# MainBoard.net
KiCad netlist of a schematic drawn in Altium Designer
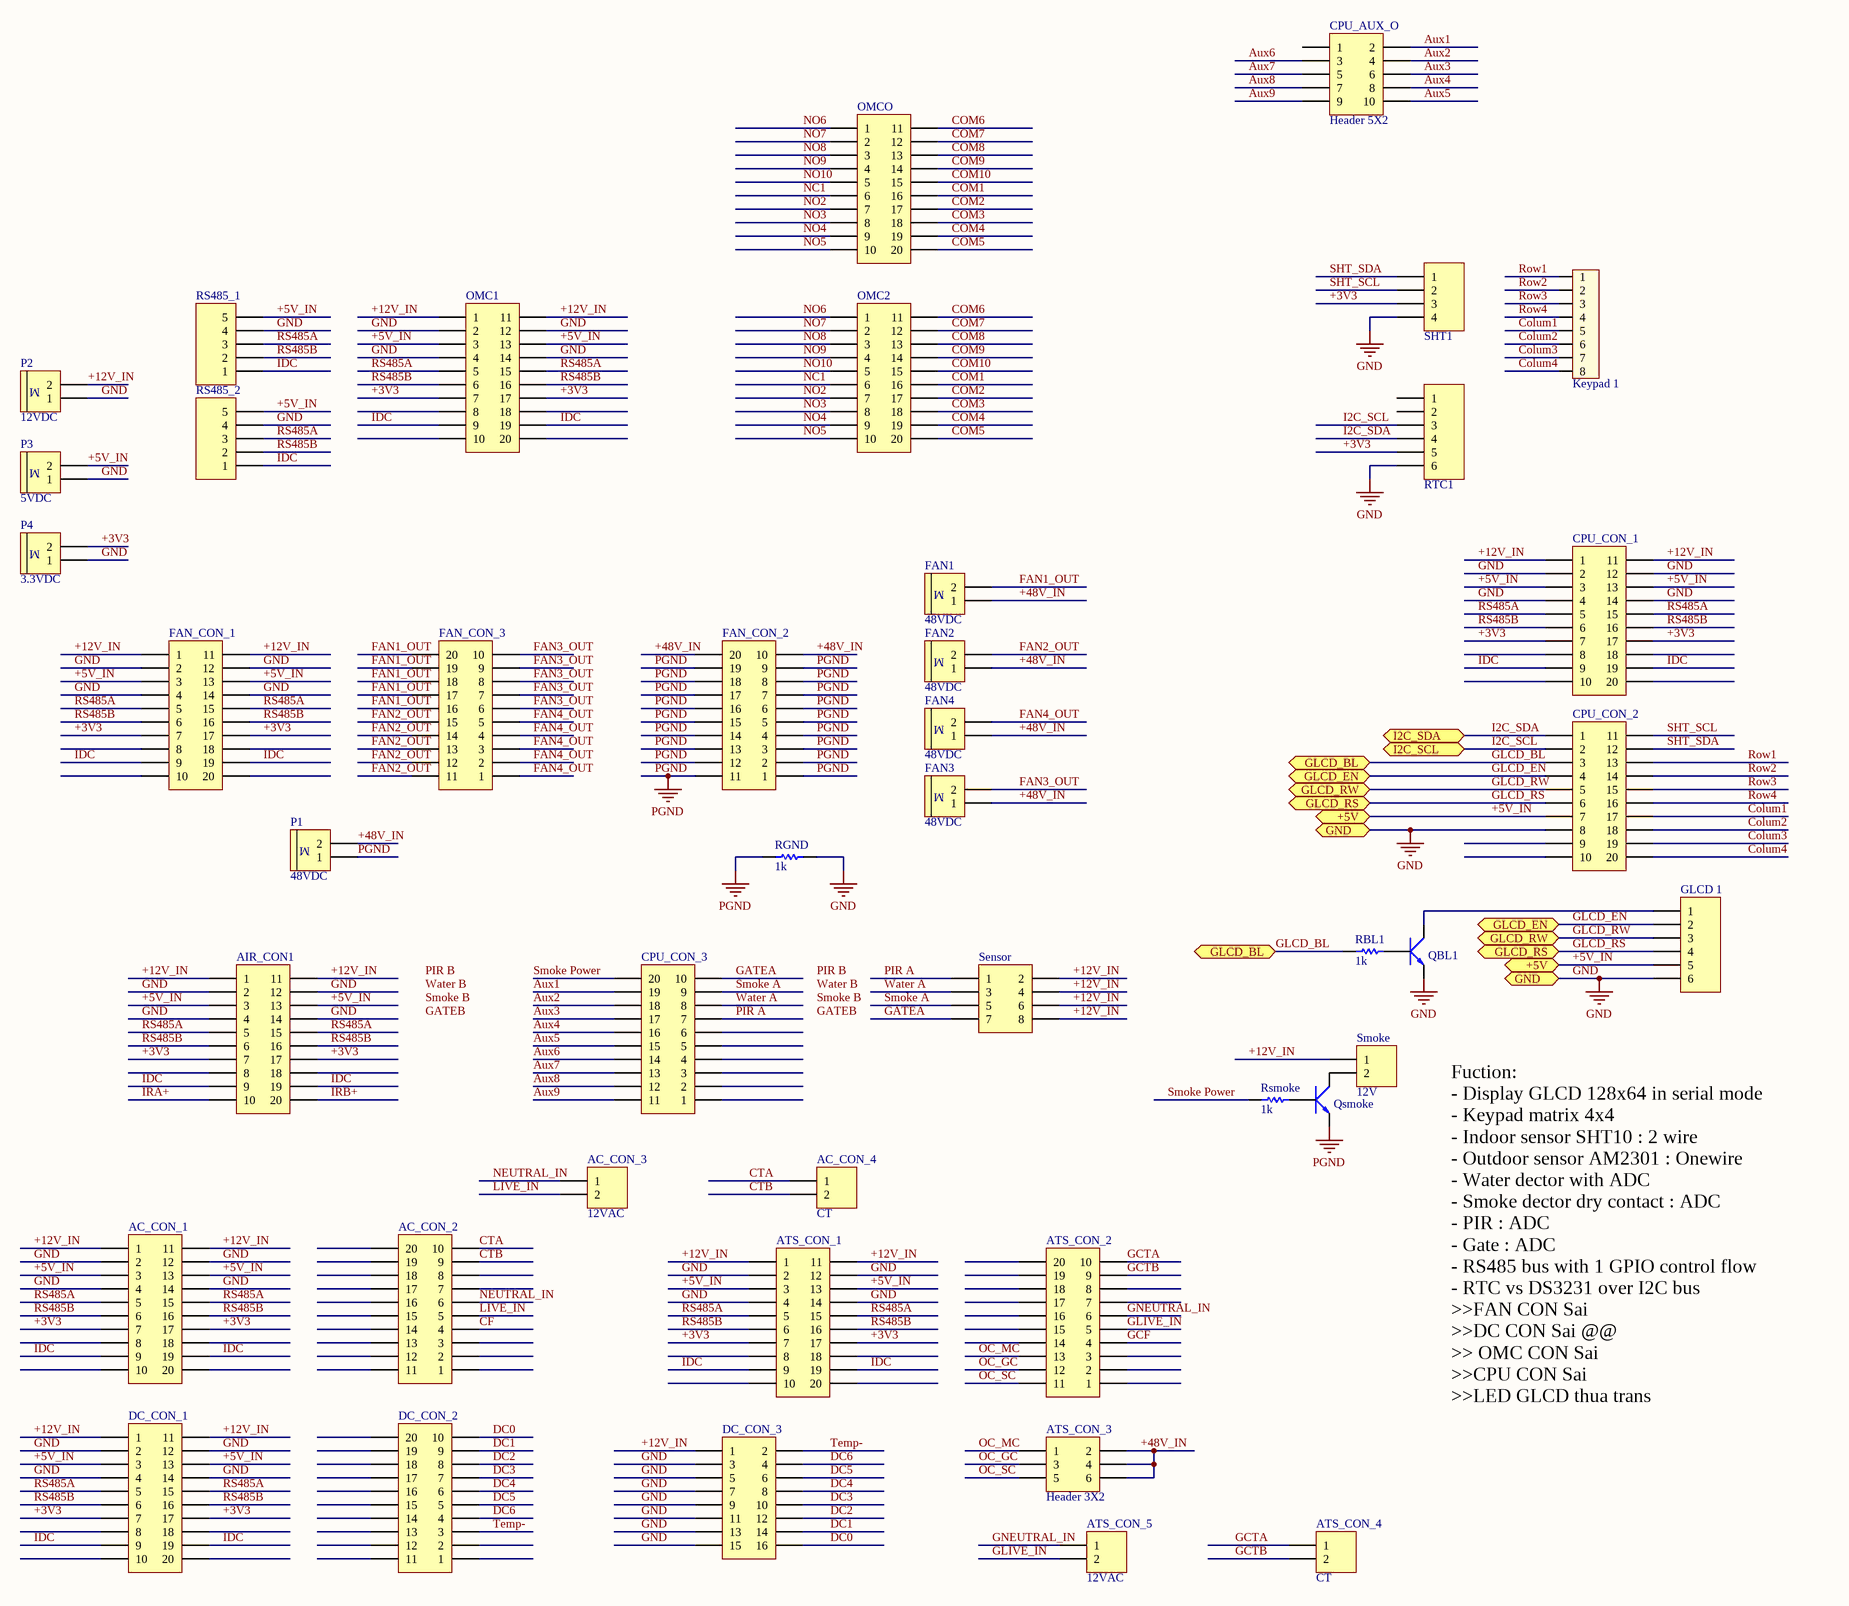
[diagram p0: MainBoard.SchDoc]

(export (version "E")
  (design (tool "Eeschema 10.0.6"))
  (components
    (comp (ref "AC_CON_1")
      (value "Header 10X2A")
      (footprint "HDR2X10_CEN")
      (description "Header, 10-Pin, Dual row")
      (libsource (lib "Miscellaneous Connectors") (part "Header 10X2A"))
    )
    (comp (ref "AC_CON_2")
      (value "Header 10X2A")
      (footprint "HDR2X10_CEN")
      (description "Header, 10-Pin, Dual row")
      (libsource (lib "") (part "Header 10X2A_1"))
    )
    (comp (ref "AC_CON_3")
      (value "12VAC")
      (footprint "HDR1X2")
      (description "Header, 2-Pin")
      (libsource (lib "Miscellaneous Connectors") (part "Header 2"))
    )
    (comp (ref "AC_CON_4")
      (value "CT")
      (footprint "HDR1X2")
      (description "Header, 2-Pin")
      (libsource (lib "Miscellaneous Connectors") (part "Header 2"))
    )
    (comp (ref "AIR_CON1")
      (value "Header 10X2A")
      (footprint "HDR2X10_CEN")
      (description "Header, 10-Pin, Dual row")
      (libsource (lib "Miscellaneous Connectors") (part "Header 10X2A"))
    )
    (comp (ref "ATS_CON_1")
      (value "Header 10X2A")
      (footprint "HDR2X10_CEN")
      (description "Header, 10-Pin, Dual row")
      (libsource (lib "Miscellaneous Connectors") (part "Header 10X2A"))
    )
    (comp (ref "ATS_CON_2")
      (value "Header 10X2A")
      (footprint "HDR2X10_CEN")
      (description "Header, 10-Pin, Dual row")
      (libsource (lib "") (part "Header 10X2A_1"))
    )
    (comp (ref "ATS_CON_3")
      (value "Header 3X2")
      (footprint "HDR2X3")
      (description "Header, 3-Pin, Dual row")
      (libsource (lib "Miscellaneous Connectors") (part "Header 3X2"))
    )
    (comp (ref "ATS_CON_4")
      (value "CT")
      (footprint "HDR1X2")
      (description "Header, 2-Pin")
      (libsource (lib "Miscellaneous Connectors") (part "Header 2"))
    )
    (comp (ref "ATS_CON_5")
      (value "12VAC")
      (footprint "HDR1X2")
      (description "Header, 2-Pin")
      (libsource (lib "Miscellaneous Connectors") (part "Header 2"))
    )
    (comp (ref "CPU_AUX_O")
      (value "Header 5X2")
      (footprint "HDR2X5")
      (description "Header, 5-Pin, Dual row")
      (libsource (lib "Miscellaneous Connectors") (part "Header 5X2"))
    )
    (comp (ref "CPU_CON_1")
      (value "Header 10X2A")
      (footprint "HDR2X10_CEN")
      (description "Header, 10-Pin, Dual row")
      (libsource (lib "Miscellaneous Connectors") (part "Header 10X2A"))
    )
    (comp (ref "CPU_CON_2")
      (value "Header 10X2A")
      (footprint "HDR2X10_CEN")
      (description "Header, 10-Pin, Dual row")
      (libsource (lib "Miscellaneous Connectors") (part "Header 10X2A"))
    )
    (comp (ref "CPU_CON_3")
      (value "Header 10X2A")
      (footprint "HDR2X10_CEN")
      (description "Header, 10-Pin, Dual row")
      (libsource (lib "") (part "Header 10X2A_1"))
    )
    (comp (ref "DC_CON_1")
      (value "Header 10X2A")
      (footprint "HDR2X10_CEN")
      (description "Header, 10-Pin, Dual row")
      (libsource (lib "Miscellaneous Connectors") (part "Header 10X2A"))
    )
    (comp (ref "DC_CON_2")
      (value "Header 10X2A")
      (footprint "HDR2X10_CEN")
      (description "Header, 10-Pin, Dual row")
      (libsource (lib "") (part "Header 10X2A_1"))
    )
    (comp (ref "DC_CON_3")
      (value "Header 8X2")
      (footprint "HDR2X8")
      (description "Header, 8-Pin, Dual row")
      (libsource (lib "Miscellaneous Connectors") (part "Header 8X2"))
    )
    (comp (ref "FAN1")
      (value "48VDC")
      (footprint "Medium - Header 2")
      (description "Header, 2-Pin, Medium")
      (libsource (lib "MH_THU VIEN CHUAN 12-03-2015") (part "Header 2 - M"))
    )
    (comp (ref "FAN2")
      (value "48VDC")
      (footprint "Medium - Header 2")
      (description "Header, 2-Pin, Medium")
      (libsource (lib "MH_THU VIEN CHUAN 12-03-2015") (part "Header 2 - M"))
    )
    (comp (ref "FAN3")
      (value "48VDC")
      (footprint "Medium - Header 2")
      (description "Header, 2-Pin, Medium")
      (libsource (lib "MH_THU VIEN CHUAN 12-03-2015") (part "Header 2 - M"))
    )
    (comp (ref "FAN4")
      (value "48VDC")
      (footprint "Medium - Header 2")
      (description "Header, 2-Pin, Medium")
      (libsource (lib "MH_THU VIEN CHUAN 12-03-2015") (part "Header 2 - M"))
    )
    (comp (ref "FAN_CON_1")
      (value "Header 10X2A")
      (footprint "HDR2X10_CEN")
      (description "Header, 10-Pin, Dual row")
      (libsource (lib "Miscellaneous Connectors") (part "Header 10X2A"))
    )
    (comp (ref "FAN_CON_2")
      (value "Header 10X2A")
      (footprint "HDR2X10_CEN")
      (description "Header, 10-Pin, Dual row")
      (libsource (lib "") (part "Header 10X2A_1"))
    )
    (comp (ref "FAN_CON_3")
      (value "Header 10X2A")
      (footprint "HDR2X10_CEN")
      (description "Header, 10-Pin, Dual row")
      (libsource (lib "") (part "Header 10X2A_1"))
    )
    (comp (ref "GLCD 1")
      (value "Header 6")
      (footprint "HDR1X6")
      (description "Header, 6-Pin")
      (libsource (lib "Miscellaneous Connectors") (part "Header 6"))
    )
    (comp (ref "Keypad 1")
      (value "JP8")
      (footprint "CON8")
      (description "Connector 8")
      (libsource (lib "syhaunguyen") (part "Con8"))
    )
    (comp (ref "OMC1")
      (value "Header 10X2A")
      (footprint "HDR2X10_CEN")
      (description "Header, 10-Pin, Dual row")
      (libsource (lib "Miscellaneous Connectors") (part "Header 10X2A"))
    )
    (comp (ref "OMC2")
      (value "Header 10X2A")
      (footprint "HDR2X10_CEN")
      (description "Header, 10-Pin, Dual row")
      (libsource (lib "Miscellaneous Connectors") (part "Header 10X2A"))
    )
    (comp (ref "OMCO")
      (value "Header 10X2A")
      (footprint "HDR2X10_CEN")
      (description "Header, 10-Pin, Dual row")
      (libsource (lib "Miscellaneous Connectors") (part "Header 10X2A"))
    )
    (comp (ref "P1")
      (value "48VDC")
      (footprint "Medium - Header 2")
      (description "Header, 2-Pin, Medium")
      (libsource (lib "MH_THU VIEN CHUAN 12-03-2015") (part "Header 2 - M"))
    )
    (comp (ref "P2")
      (value "12VDC")
      (footprint "Medium - Header 2")
      (description "Header, 2-Pin, Medium")
      (libsource (lib "MH_THU VIEN CHUAN 12-03-2015") (part "Header 2 - M"))
    )
    (comp (ref "P3")
      (value "5VDC")
      (footprint "Medium - Header 2")
      (description "Header, 2-Pin, Medium")
      (libsource (lib "MH_THU VIEN CHUAN 12-03-2015") (part "Header 2 - M"))
    )
    (comp (ref "P4")
      (value "3.3VDC")
      (footprint "Medium - Header 2")
      (description "Header, 2-Pin, Medium")
      (libsource (lib "MH_THU VIEN CHUAN 12-03-2015") (part "Header 2 - M"))
    )
    (comp (ref "QBL1")
      (value "C828")
      (footprint "QTO-92B")
      (description "Transistor C828 C1815....")
      (libsource (lib "Tuan") (part "NPN"))
    )
    (comp (ref "Qsmoke")
      (value "C828")
      (footprint "QTO-92B")
      (description "Transistor C828 C1815....")
      (libsource (lib "Tuan") (part "NPN"))
    )
    (comp (ref "RBL1")
      (value "1k")
      (footprint "AXIAL-0.4")
      (fields (field (name "Comment") "Res"))
      (libsource (lib "Tuan") (part "Res"))
    )
    (comp (ref "RGND")
      (value "1k")
      (footprint "AXIAL-0.4")
      (fields (field (name "Comment") "Res"))
      (libsource (lib "Tuan") (part "Res"))
    )
    (comp (ref "RS485_1")
      (value "Header 5")
      (footprint "HDR1X5")
      (description "Header, 5-Pin")
      (libsource (lib "Miscellaneous Connectors") (part "Header 5"))
    )
    (comp (ref "RS485_2")
      (value "Header 5")
      (footprint "HDR1X5")
      (description "Header, 5-Pin")
      (libsource (lib "Miscellaneous Connectors") (part "Header 5"))
    )
    (comp (ref "Rsmoke")
      (value "1k")
      (footprint "AXIAL-0.4")
      (fields (field (name "Comment") "Res"))
      (libsource (lib "Tuan") (part "Res"))
    )
    (comp (ref "RTC1")
      (value "Header 6")
      (footprint "heromap:HDR1X6")
      (description "Header, 6-Pin")
      (libsource (lib "heromap") (part "Header 6"))
    )
    (comp (ref "Sensor")
      (value "Header 4X2")
      (footprint "HDR2X4")
      (description "Header, 4-Pin, Dual row")
      (libsource (lib "Miscellaneous Connectors") (part "Header 4X2"))
    )
    (comp (ref "SHT1")
      (value "Header 4")
      (footprint "heromap:HDR1X4")
      (description "Header, 4-Pin")
      (libsource (lib "heromap") (part "Header 4"))
    )
    (comp (ref "Smoke")
      (value "12V")
      (footprint "HDR1X2")
      (description "Header, 2-Pin")
      (libsource (lib "Miscellaneous Connectors") (part "Header 2"))
    )
  )
  (nets
    (net (code "1") (name "/+3V3") (class "Default")
      (node (ref "AC_CON_1") (pin "17") (pinfunction "17_17") (pintype "passive"))
      (node (ref "AC_CON_1") (pin "7") (pinfunction "7_7") (pintype "passive"))
      (node (ref "AIR_CON1") (pin "17") (pinfunction "17_17") (pintype "passive"))
      (node (ref "AIR_CON1") (pin "7") (pinfunction "7_7") (pintype "passive"))
      (node (ref "ATS_CON_1") (pin "17") (pinfunction "17_17") (pintype "passive"))
      (node (ref "ATS_CON_1") (pin "7") (pinfunction "7_7") (pintype "passive"))
      (node (ref "CPU_CON_1") (pin "17") (pinfunction "17_17") (pintype "passive"))
      (node (ref "CPU_CON_1") (pin "7") (pinfunction "7_7") (pintype "passive"))
      (node (ref "DC_CON_1") (pin "17") (pinfunction "17_17") (pintype "passive"))
      (node (ref "DC_CON_1") (pin "7") (pinfunction "7_7") (pintype "passive"))
      (node (ref "FAN_CON_1") (pin "17") (pinfunction "17_17") (pintype "passive"))
      (node (ref "FAN_CON_1") (pin "7") (pinfunction "7_7") (pintype "passive"))
      (node (ref "OMC1") (pin "17") (pinfunction "17_17") (pintype "passive"))
      (node (ref "OMC1") (pin "7") (pinfunction "7_7") (pintype "passive"))
      (node (ref "P4") (pin "2") (pinfunction "2_2") (pintype "passive"))
      (node (ref "RTC1") (pin "5") (pinfunction "5_5") (pintype "passive"))
      (node (ref "SHT1") (pin "3") (pinfunction "3_3") (pintype "passive"))
    )
    (net (code "2") (name "/+5V_IN") (class "Default")
      (node (ref "AC_CON_1") (pin "13") (pinfunction "13_13") (pintype "passive"))
      (node (ref "AC_CON_1") (pin "3") (pinfunction "3_3") (pintype "passive"))
      (node (ref "AIR_CON1") (pin "13") (pinfunction "13_13") (pintype "passive"))
      (node (ref "AIR_CON1") (pin "3") (pinfunction "3_3") (pintype "passive"))
      (node (ref "ATS_CON_1") (pin "13") (pinfunction "13_13") (pintype "passive"))
      (node (ref "ATS_CON_1") (pin "3") (pinfunction "3_3") (pintype "passive"))
      (node (ref "CPU_CON_1") (pin "13") (pinfunction "13_13") (pintype "passive"))
      (node (ref "CPU_CON_1") (pin "3") (pinfunction "3_3") (pintype "passive"))
      (node (ref "CPU_CON_2") (pin "7") (pinfunction "7_7") (pintype "passive"))
      (node (ref "DC_CON_1") (pin "13") (pinfunction "13_13") (pintype "passive"))
      (node (ref "DC_CON_1") (pin "3") (pinfunction "3_3") (pintype "passive"))
      (node (ref "FAN_CON_1") (pin "13") (pinfunction "13_13") (pintype "passive"))
      (node (ref "FAN_CON_1") (pin "3") (pinfunction "3_3") (pintype "passive"))
      (node (ref "GLCD 1") (pin "5") (pinfunction "5_5") (pintype "passive"))
      (node (ref "OMC1") (pin "13") (pinfunction "13_13") (pintype "passive"))
      (node (ref "OMC1") (pin "3") (pinfunction "3_3") (pintype "passive"))
      (node (ref "P3") (pin "2") (pinfunction "2_2") (pintype "passive"))
      (node (ref "RS485_1") (pin "5") (pinfunction "5_5") (pintype "passive"))
      (node (ref "RS485_2") (pin "5") (pinfunction "5_5") (pintype "passive"))
    )
    (net (code "3") (name "/+12V_IN") (class "Default")
      (node (ref "AC_CON_1") (pin "1") (pinfunction "1_1") (pintype "passive"))
      (node (ref "AC_CON_1") (pin "11") (pinfunction "11_11") (pintype "passive"))
      (node (ref "AIR_CON1") (pin "1") (pinfunction "1_1") (pintype "passive"))
      (node (ref "AIR_CON1") (pin "11") (pinfunction "11_11") (pintype "passive"))
      (node (ref "ATS_CON_1") (pin "1") (pinfunction "1_1") (pintype "passive"))
      (node (ref "ATS_CON_1") (pin "11") (pinfunction "11_11") (pintype "passive"))
      (node (ref "CPU_CON_1") (pin "1") (pinfunction "1_1") (pintype "passive"))
      (node (ref "CPU_CON_1") (pin "11") (pinfunction "11_11") (pintype "passive"))
      (node (ref "DC_CON_1") (pin "1") (pinfunction "1_1") (pintype "passive"))
      (node (ref "DC_CON_1") (pin "11") (pinfunction "11_11") (pintype "passive"))
      (node (ref "DC_CON_3") (pin "1") (pinfunction "1_1") (pintype "passive"))
      (node (ref "FAN_CON_1") (pin "1") (pinfunction "1_1") (pintype "passive"))
      (node (ref "FAN_CON_1") (pin "11") (pinfunction "11_11") (pintype "passive"))
      (node (ref "OMC1") (pin "1") (pinfunction "1_1") (pintype "passive"))
      (node (ref "OMC1") (pin "11") (pinfunction "11_11") (pintype "passive"))
      (node (ref "P2") (pin "2") (pinfunction "2_2") (pintype "passive"))
      (node (ref "Sensor") (pin "2") (pinfunction "2_2") (pintype "passive"))
      (node (ref "Sensor") (pin "4") (pinfunction "4_4") (pintype "passive"))
      (node (ref "Sensor") (pin "6") (pinfunction "6_6") (pintype "passive"))
      (node (ref "Sensor") (pin "8") (pinfunction "8_8") (pintype "passive"))
      (node (ref "Smoke") (pin "1") (pinfunction "1_1") (pintype "passive"))
    )
    (net (code "4") (name "/+48V_IN") (class "Default")
      (node (ref "ATS_CON_3") (pin "2") (pinfunction "2_2") (pintype "passive"))
      (node (ref "ATS_CON_3") (pin "4") (pinfunction "4_4") (pintype "passive"))
      (node (ref "ATS_CON_3") (pin "6") (pinfunction "6_6") (pintype "passive"))
      (node (ref "FAN1") (pin "1") (pinfunction "1_1") (pintype "passive"))
      (node (ref "FAN2") (pin "1") (pinfunction "1_1") (pintype "passive"))
      (node (ref "FAN3") (pin "1") (pinfunction "1_1") (pintype "passive"))
      (node (ref "FAN4") (pin "1") (pinfunction "1_1") (pintype "passive"))
      (node (ref "FAN_CON_2") (pin "10") (pinfunction "10_10") (pintype "passive"))
      (node (ref "FAN_CON_2") (pin "20") (pinfunction "20_20") (pintype "passive"))
      (node (ref "P1") (pin "2") (pinfunction "2_2") (pintype "passive"))
    )
    (net (code "5") (name "/Aux1") (class "Default")
      (node (ref "CPU_AUX_O") (pin "2") (pinfunction "2_2") (pintype "passive"))
      (node (ref "CPU_CON_3") (pin "19") (pinfunction "19_19") (pintype "passive"))
    )
    (net (code "6") (name "/Aux2") (class "Default")
      (node (ref "CPU_AUX_O") (pin "4") (pinfunction "4_4") (pintype "passive"))
      (node (ref "CPU_CON_3") (pin "18") (pinfunction "18_18") (pintype "passive"))
    )
    (net (code "7") (name "/Aux3") (class "Default")
      (node (ref "CPU_AUX_O") (pin "6") (pinfunction "6_6") (pintype "passive"))
      (node (ref "CPU_CON_3") (pin "17") (pinfunction "17_17") (pintype "passive"))
    )
    (net (code "8") (name "/Aux4") (class "Default")
      (node (ref "CPU_AUX_O") (pin "8") (pinfunction "8_8") (pintype "passive"))
      (node (ref "CPU_CON_3") (pin "16") (pinfunction "16_16") (pintype "passive"))
    )
    (net (code "9") (name "/Aux5") (class "Default")
      (node (ref "CPU_AUX_O") (pin "10") (pinfunction "10_10") (pintype "passive"))
      (node (ref "CPU_CON_3") (pin "15") (pinfunction "15_15") (pintype "passive"))
    )
    (net (code "10") (name "/Aux6") (class "Default")
      (node (ref "CPU_AUX_O") (pin "3") (pinfunction "3_3") (pintype "passive"))
      (node (ref "CPU_CON_3") (pin "14") (pinfunction "14_14") (pintype "passive"))
    )
    (net (code "11") (name "/Aux7") (class "Default")
      (node (ref "CPU_AUX_O") (pin "5") (pinfunction "5_5") (pintype "passive"))
      (node (ref "CPU_CON_3") (pin "13") (pinfunction "13_13") (pintype "passive"))
    )
    (net (code "12") (name "/Aux8") (class "Default")
      (node (ref "CPU_AUX_O") (pin "7") (pinfunction "7_7") (pintype "passive"))
      (node (ref "CPU_CON_3") (pin "12") (pinfunction "12_12") (pintype "passive"))
    )
    (net (code "13") (name "/Aux9") (class "Default")
      (node (ref "CPU_AUX_O") (pin "9") (pinfunction "9_9") (pintype "passive"))
      (node (ref "CPU_CON_3") (pin "11") (pinfunction "11_11") (pintype "passive"))
    )
    (net (code "14") (name "/CF") (class "Default")
      (node (ref "AC_CON_2") (pin "4") (pinfunction "4_4") (pintype "passive"))
    )
    (net (code "15") (name "/COM1") (class "Default")
      (node (ref "OMC2") (pin "16") (pinfunction "16_16") (pintype "passive"))
      (node (ref "OMCO") (pin "16") (pinfunction "16_16") (pintype "passive"))
    )
    (net (code "16") (name "/COM2") (class "Default")
      (node (ref "OMC2") (pin "17") (pinfunction "17_17") (pintype "passive"))
      (node (ref "OMCO") (pin "17") (pinfunction "17_17") (pintype "passive"))
    )
    (net (code "17") (name "/COM3") (class "Default")
      (node (ref "OMC2") (pin "18") (pinfunction "18_18") (pintype "passive"))
      (node (ref "OMCO") (pin "18") (pinfunction "18_18") (pintype "passive"))
    )
    (net (code "18") (name "/COM4") (class "Default")
      (node (ref "OMC2") (pin "19") (pinfunction "19_19") (pintype "passive"))
      (node (ref "OMCO") (pin "19") (pinfunction "19_19") (pintype "passive"))
    )
    (net (code "19") (name "/COM5") (class "Default")
      (node (ref "OMC2") (pin "20") (pinfunction "20_20") (pintype "passive"))
      (node (ref "OMCO") (pin "20") (pinfunction "20_20") (pintype "passive"))
    )
    (net (code "20") (name "/COM6") (class "Default")
      (node (ref "OMC2") (pin "11") (pinfunction "11_11") (pintype "passive"))
      (node (ref "OMCO") (pin "11") (pinfunction "11_11") (pintype "passive"))
    )
    (net (code "21") (name "/COM7") (class "Default")
      (node (ref "OMC2") (pin "12") (pinfunction "12_12") (pintype "passive"))
      (node (ref "OMCO") (pin "12") (pinfunction "12_12") (pintype "passive"))
    )
    (net (code "22") (name "/COM8") (class "Default")
      (node (ref "OMC2") (pin "13") (pinfunction "13_13") (pintype "passive"))
      (node (ref "OMCO") (pin "13") (pinfunction "13_13") (pintype "passive"))
    )
    (net (code "23") (name "/COM9") (class "Default")
      (node (ref "OMC2") (pin "14") (pinfunction "14_14") (pintype "passive"))
      (node (ref "OMCO") (pin "14") (pinfunction "14_14") (pintype "passive"))
    )
    (net (code "24") (name "/COM10") (class "Default")
      (node (ref "OMC2") (pin "15") (pinfunction "15_15") (pintype "passive"))
      (node (ref "OMCO") (pin "15") (pinfunction "15_15") (pintype "passive"))
    )
    (net (code "25") (name "/CTA") (class "Default")
      (node (ref "AC_CON_2") (pin "10") (pinfunction "10_10") (pintype "passive"))
      (node (ref "AC_CON_4") (pin "1") (pinfunction "1_1") (pintype "passive"))
    )
    (net (code "26") (name "/CTB") (class "Default")
      (node (ref "AC_CON_2") (pin "9") (pinfunction "9_9") (pintype "passive"))
      (node (ref "AC_CON_4") (pin "2") (pinfunction "2_2") (pintype "passive"))
    )
    (net (code "27") (name "/Colum1") (class "Default")
      (node (ref "CPU_CON_2") (pin "17") (pinfunction "17_17") (pintype "passive"))
      (node (ref "Keypad 1") (pin "5") (pinfunction "5_5") (pintype "passive"))
    )
    (net (code "28") (name "/Colum2") (class "Default")
      (node (ref "CPU_CON_2") (pin "18") (pinfunction "18_18") (pintype "passive"))
      (node (ref "Keypad 1") (pin "6") (pinfunction "6_6") (pintype "passive"))
    )
    (net (code "29") (name "/Colum3") (class "Default")
      (node (ref "CPU_CON_2") (pin "19") (pinfunction "19_19") (pintype "passive"))
      (node (ref "Keypad 1") (pin "7") (pinfunction "7_7") (pintype "passive"))
    )
    (net (code "30") (name "/Colum4") (class "Default")
      (node (ref "CPU_CON_2") (pin "20") (pinfunction "20_20") (pintype "passive"))
      (node (ref "Keypad 1") (pin "8") (pinfunction "8_8") (pintype "passive"))
    )
    (net (code "31") (name "/DC0") (class "Default")
      (node (ref "DC_CON_2") (pin "10") (pinfunction "10_10") (pintype "passive"))
      (node (ref "DC_CON_3") (pin "16") (pinfunction "16_16") (pintype "passive"))
    )
    (net (code "32") (name "/DC1") (class "Default")
      (node (ref "DC_CON_2") (pin "9") (pinfunction "9_9") (pintype "passive"))
      (node (ref "DC_CON_3") (pin "14") (pinfunction "14_14") (pintype "passive"))
    )
    (net (code "33") (name "/DC2") (class "Default")
      (node (ref "DC_CON_2") (pin "8") (pinfunction "8_8") (pintype "passive"))
      (node (ref "DC_CON_3") (pin "12") (pinfunction "12_12") (pintype "passive"))
    )
    (net (code "34") (name "/DC3") (class "Default")
      (node (ref "DC_CON_2") (pin "7") (pinfunction "7_7") (pintype "passive"))
      (node (ref "DC_CON_3") (pin "10") (pinfunction "10_10") (pintype "passive"))
    )
    (net (code "35") (name "/DC4") (class "Default")
      (node (ref "DC_CON_2") (pin "6") (pinfunction "6_6") (pintype "passive"))
      (node (ref "DC_CON_3") (pin "8") (pinfunction "8_8") (pintype "passive"))
    )
    (net (code "36") (name "/DC5") (class "Default")
      (node (ref "DC_CON_2") (pin "5") (pinfunction "5_5") (pintype "passive"))
      (node (ref "DC_CON_3") (pin "6") (pinfunction "6_6") (pintype "passive"))
    )
    (net (code "37") (name "/DC6") (class "Default")
      (node (ref "DC_CON_2") (pin "4") (pinfunction "4_4") (pintype "passive"))
      (node (ref "DC_CON_3") (pin "4") (pinfunction "4_4") (pintype "passive"))
    )
    (net (code "38") (name "/FAN1_OUT") (class "Default")
      (node (ref "FAN1") (pin "2") (pinfunction "2_2") (pintype "passive"))
      (node (ref "FAN_CON_3") (pin "16") (pinfunction "16_16") (pintype "passive"))
      (node (ref "FAN_CON_3") (pin "17") (pinfunction "17_17") (pintype "passive"))
      (node (ref "FAN_CON_3") (pin "18") (pinfunction "18_18") (pintype "passive"))
      (node (ref "FAN_CON_3") (pin "19") (pinfunction "19_19") (pintype "passive"))
      (node (ref "FAN_CON_3") (pin "20") (pinfunction "20_20") (pintype "passive"))
    )
    (net (code "39") (name "/FAN2_OUT") (class "Default")
      (node (ref "FAN2") (pin "2") (pinfunction "2_2") (pintype "passive"))
      (node (ref "FAN_CON_3") (pin "11") (pinfunction "11_11") (pintype "passive"))
      (node (ref "FAN_CON_3") (pin "12") (pinfunction "12_12") (pintype "passive"))
      (node (ref "FAN_CON_3") (pin "13") (pinfunction "13_13") (pintype "passive"))
      (node (ref "FAN_CON_3") (pin "14") (pinfunction "14_14") (pintype "passive"))
      (node (ref "FAN_CON_3") (pin "15") (pinfunction "15_15") (pintype "passive"))
    )
    (net (code "40") (name "/FAN3_OUT") (class "Default")
      (node (ref "FAN3") (pin "2") (pinfunction "2_2") (pintype "passive"))
      (node (ref "FAN_CON_3") (pin "10") (pinfunction "10_10") (pintype "passive"))
      (node (ref "FAN_CON_3") (pin "6") (pinfunction "6_6") (pintype "passive"))
      (node (ref "FAN_CON_3") (pin "7") (pinfunction "7_7") (pintype "passive"))
      (node (ref "FAN_CON_3") (pin "8") (pinfunction "8_8") (pintype "passive"))
      (node (ref "FAN_CON_3") (pin "9") (pinfunction "9_9") (pintype "passive"))
    )
    (net (code "41") (name "/FAN4_OUT") (class "Default")
      (node (ref "FAN4") (pin "2") (pinfunction "2_2") (pintype "passive"))
      (node (ref "FAN_CON_3") (pin "1") (pinfunction "1_1") (pintype "passive"))
      (node (ref "FAN_CON_3") (pin "2") (pinfunction "2_2") (pintype "passive"))
      (node (ref "FAN_CON_3") (pin "3") (pinfunction "3_3") (pintype "passive"))
      (node (ref "FAN_CON_3") (pin "4") (pinfunction "4_4") (pintype "passive"))
      (node (ref "FAN_CON_3") (pin "5") (pinfunction "5_5") (pintype "passive"))
    )
    (net (code "42") (name "/GATEA") (class "Default")
      (node (ref "CPU_CON_3") (pin "10") (pinfunction "10_10") (pintype "passive"))
      (node (ref "Sensor") (pin "7") (pinfunction "7_7") (pintype "passive"))
    )
    (net (code "44") (name "/GCF") (class "Default")
      (node (ref "ATS_CON_2") (pin "4") (pinfunction "4_4") (pintype "passive"))
    )
    (net (code "45") (name "/GCTA") (class "Default")
      (node (ref "ATS_CON_2") (pin "10") (pinfunction "10_10") (pintype "passive"))
      (node (ref "ATS_CON_4") (pin "1") (pinfunction "1_1") (pintype "passive"))
    )
    (net (code "46") (name "/GCTB") (class "Default")
      (node (ref "ATS_CON_2") (pin "9") (pinfunction "9_9") (pintype "passive"))
      (node (ref "ATS_CON_4") (pin "2") (pinfunction "2_2") (pintype "passive"))
    )
    (net (code "47") (name "/GLCD_BL") (class "Default")
      (node (ref "CPU_CON_2") (pin "3") (pinfunction "3_3") (pintype "passive"))
      (node (ref "RBL1") (pin "1") (pinfunction "1_1") (pintype "passive"))
    )
    (net (code "48") (name "/GLCD_EN") (class "Default")
      (node (ref "CPU_CON_2") (pin "4") (pinfunction "4_4") (pintype "passive"))
      (node (ref "GLCD 1") (pin "2") (pinfunction "2_2") (pintype "passive"))
    )
    (net (code "49") (name "/GLCD_RS") (class "Default")
      (node (ref "CPU_CON_2") (pin "6") (pinfunction "6_6") (pintype "passive"))
      (node (ref "GLCD 1") (pin "4") (pinfunction "4_4") (pintype "passive"))
    )
    (net (code "50") (name "/GLCD_RW") (class "Default")
      (node (ref "CPU_CON_2") (pin "5") (pinfunction "5_5") (pintype "passive"))
      (node (ref "GLCD 1") (pin "3") (pinfunction "3_3") (pintype "passive"))
    )
    (net (code "51") (name "/GLIVE_IN") (class "Default")
      (node (ref "ATS_CON_2") (pin "5") (pinfunction "5_5") (pintype "passive"))
      (node (ref "ATS_CON_5") (pin "2") (pinfunction "2_2") (pintype "passive"))
    )
    (net (code "52") (name "/GNEUTRAL_IN") (class "Default")
      (node (ref "ATS_CON_2") (pin "6") (pinfunction "6_6") (pintype "passive"))
      (node (ref "ATS_CON_5") (pin "1") (pinfunction "1_1") (pintype "passive"))
    )
    (net (code "53") (name "/I2C_SCL") (class "Default")
      (node (ref "CPU_CON_2") (pin "2") (pinfunction "2_2") (pintype "passive"))
      (node (ref "RTC1") (pin "3") (pinfunction "3_3") (pintype "passive"))
    )
    (net (code "54") (name "/I2C_SDA") (class "Default")
      (node (ref "CPU_CON_2") (pin "1") (pinfunction "1_1") (pintype "passive"))
      (node (ref "RTC1") (pin "4") (pinfunction "4_4") (pintype "passive"))
    )
    (net (code "55") (name "/IDC") (class "Default")
      (node (ref "AC_CON_1") (pin "19") (pinfunction "19_19") (pintype "passive"))
      (node (ref "AC_CON_1") (pin "9") (pinfunction "9_9") (pintype "passive"))
      (node (ref "AIR_CON1") (pin "19") (pinfunction "19_19") (pintype "passive"))
      (node (ref "AIR_CON1") (pin "9") (pinfunction "9_9") (pintype "passive"))
      (node (ref "ATS_CON_1") (pin "19") (pinfunction "19_19") (pintype "passive"))
      (node (ref "ATS_CON_1") (pin "9") (pinfunction "9_9") (pintype "passive"))
      (node (ref "CPU_CON_1") (pin "19") (pinfunction "19_19") (pintype "passive"))
      (node (ref "CPU_CON_1") (pin "9") (pinfunction "9_9") (pintype "passive"))
      (node (ref "DC_CON_1") (pin "19") (pinfunction "19_19") (pintype "passive"))
      (node (ref "DC_CON_1") (pin "9") (pinfunction "9_9") (pintype "passive"))
      (node (ref "FAN_CON_1") (pin "19") (pinfunction "19_19") (pintype "passive"))
      (node (ref "FAN_CON_1") (pin "9") (pinfunction "9_9") (pintype "passive"))
      (node (ref "OMC1") (pin "19") (pinfunction "19_19") (pintype "passive"))
      (node (ref "OMC1") (pin "9") (pinfunction "9_9") (pintype "passive"))
      (node (ref "RS485_1") (pin "1") (pinfunction "1_1") (pintype "passive"))
      (node (ref "RS485_2") (pin "1") (pinfunction "1_1") (pintype "passive"))
    )
    (net (code "56") (name "/IRA+") (class "Default")
      (node (ref "AIR_CON1") (pin "10") (pinfunction "10_10") (pintype "passive"))
    )
    (net (code "57") (name "/IRB+") (class "Default")
      (node (ref "AIR_CON1") (pin "20") (pinfunction "20_20") (pintype "passive"))
    )
    (net (code "58") (name "/LIVE_IN") (class "Default")
      (node (ref "AC_CON_2") (pin "5") (pinfunction "5_5") (pintype "passive"))
      (node (ref "AC_CON_3") (pin "2") (pinfunction "2_2") (pintype "passive"))
    )
    (net (code "59") (name "/NC1") (class "Default")
      (node (ref "OMC2") (pin "6") (pinfunction "6_6") (pintype "passive"))
      (node (ref "OMCO") (pin "6") (pinfunction "6_6") (pintype "passive"))
    )
    (net (code "60") (name "/NEUTRAL_IN") (class "Default")
      (node (ref "AC_CON_2") (pin "6") (pinfunction "6_6") (pintype "passive"))
      (node (ref "AC_CON_3") (pin "1") (pinfunction "1_1") (pintype "passive"))
    )
    (net (code "61") (name "/NO2") (class "Default")
      (node (ref "OMC2") (pin "7") (pinfunction "7_7") (pintype "passive"))
      (node (ref "OMCO") (pin "7") (pinfunction "7_7") (pintype "passive"))
    )
    (net (code "62") (name "/NO3") (class "Default")
      (node (ref "OMC2") (pin "8") (pinfunction "8_8") (pintype "passive"))
      (node (ref "OMCO") (pin "8") (pinfunction "8_8") (pintype "passive"))
    )
    (net (code "63") (name "/NO4") (class "Default")
      (node (ref "OMC2") (pin "9") (pinfunction "9_9") (pintype "passive"))
      (node (ref "OMCO") (pin "9") (pinfunction "9_9") (pintype "passive"))
    )
    (net (code "64") (name "/NO5") (class "Default")
      (node (ref "OMC2") (pin "10") (pinfunction "10_10") (pintype "passive"))
      (node (ref "OMCO") (pin "10") (pinfunction "10_10") (pintype "passive"))
    )
    (net (code "65") (name "/NO6") (class "Default")
      (node (ref "OMC2") (pin "1") (pinfunction "1_1") (pintype "passive"))
      (node (ref "OMCO") (pin "1") (pinfunction "1_1") (pintype "passive"))
    )
    (net (code "66") (name "/NO7") (class "Default")
      (node (ref "OMC2") (pin "2") (pinfunction "2_2") (pintype "passive"))
      (node (ref "OMCO") (pin "2") (pinfunction "2_2") (pintype "passive"))
    )
    (net (code "67") (name "/NO8") (class "Default")
      (node (ref "OMC2") (pin "3") (pinfunction "3_3") (pintype "passive"))
      (node (ref "OMCO") (pin "3") (pinfunction "3_3") (pintype "passive"))
    )
    (net (code "68") (name "/NO9") (class "Default")
      (node (ref "OMC2") (pin "4") (pinfunction "4_4") (pintype "passive"))
      (node (ref "OMCO") (pin "4") (pinfunction "4_4") (pintype "passive"))
    )
    (net (code "69") (name "/NO10") (class "Default")
      (node (ref "OMC2") (pin "5") (pinfunction "5_5") (pintype "passive"))
      (node (ref "OMCO") (pin "5") (pinfunction "5_5") (pintype "passive"))
    )
    (net (code "70") (name "/OC_GC") (class "Default")
      (node (ref "ATS_CON_2") (pin "12") (pinfunction "12_12") (pintype "passive"))
      (node (ref "ATS_CON_3") (pin "3") (pinfunction "3_3") (pintype "passive"))
    )
    (net (code "71") (name "/OC_MC") (class "Default")
      (node (ref "ATS_CON_2") (pin "13") (pinfunction "13_13") (pintype "passive"))
      (node (ref "ATS_CON_3") (pin "1") (pinfunction "1_1") (pintype "passive"))
    )
    (net (code "72") (name "/OC_SC") (class "Default")
      (node (ref "ATS_CON_2") (pin "11") (pinfunction "11_11") (pintype "passive"))
      (node (ref "ATS_CON_3") (pin "5") (pinfunction "5_5") (pintype "passive"))
    )
    (net (code "73") (name "/PIR A") (class "Default")
      (node (ref "CPU_CON_3") (pin "7") (pinfunction "7_7") (pintype "passive"))
      (node (ref "Sensor") (pin "1") (pinfunction "1_1") (pintype "passive"))
    )
    (net (code "75") (name "/RS485A") (class "Default")
      (node (ref "AC_CON_1") (pin "15") (pinfunction "15_15") (pintype "passive"))
      (node (ref "AC_CON_1") (pin "5") (pinfunction "5_5") (pintype "passive"))
      (node (ref "AIR_CON1") (pin "15") (pinfunction "15_15") (pintype "passive"))
      (node (ref "AIR_CON1") (pin "5") (pinfunction "5_5") (pintype "passive"))
      (node (ref "ATS_CON_1") (pin "15") (pinfunction "15_15") (pintype "passive"))
      (node (ref "ATS_CON_1") (pin "5") (pinfunction "5_5") (pintype "passive"))
      (node (ref "CPU_CON_1") (pin "15") (pinfunction "15_15") (pintype "passive"))
      (node (ref "CPU_CON_1") (pin "5") (pinfunction "5_5") (pintype "passive"))
      (node (ref "DC_CON_1") (pin "15") (pinfunction "15_15") (pintype "passive"))
      (node (ref "DC_CON_1") (pin "5") (pinfunction "5_5") (pintype "passive"))
      (node (ref "FAN_CON_1") (pin "15") (pinfunction "15_15") (pintype "passive"))
      (node (ref "FAN_CON_1") (pin "5") (pinfunction "5_5") (pintype "passive"))
      (node (ref "OMC1") (pin "15") (pinfunction "15_15") (pintype "passive"))
      (node (ref "OMC1") (pin "5") (pinfunction "5_5") (pintype "passive"))
      (node (ref "RS485_1") (pin "3") (pinfunction "3_3") (pintype "passive"))
      (node (ref "RS485_2") (pin "3") (pinfunction "3_3") (pintype "passive"))
    )
    (net (code "76") (name "/RS485B") (class "Default")
      (node (ref "AC_CON_1") (pin "16") (pinfunction "16_16") (pintype "passive"))
      (node (ref "AC_CON_1") (pin "6") (pinfunction "6_6") (pintype "passive"))
      (node (ref "AIR_CON1") (pin "16") (pinfunction "16_16") (pintype "passive"))
      (node (ref "AIR_CON1") (pin "6") (pinfunction "6_6") (pintype "passive"))
      (node (ref "ATS_CON_1") (pin "16") (pinfunction "16_16") (pintype "passive"))
      (node (ref "ATS_CON_1") (pin "6") (pinfunction "6_6") (pintype "passive"))
      (node (ref "CPU_CON_1") (pin "16") (pinfunction "16_16") (pintype "passive"))
      (node (ref "CPU_CON_1") (pin "6") (pinfunction "6_6") (pintype "passive"))
      (node (ref "DC_CON_1") (pin "16") (pinfunction "16_16") (pintype "passive"))
      (node (ref "DC_CON_1") (pin "6") (pinfunction "6_6") (pintype "passive"))
      (node (ref "FAN_CON_1") (pin "16") (pinfunction "16_16") (pintype "passive"))
      (node (ref "FAN_CON_1") (pin "6") (pinfunction "6_6") (pintype "passive"))
      (node (ref "OMC1") (pin "16") (pinfunction "16_16") (pintype "passive"))
      (node (ref "OMC1") (pin "6") (pinfunction "6_6") (pintype "passive"))
      (node (ref "RS485_1") (pin "2") (pinfunction "2_2") (pintype "passive"))
      (node (ref "RS485_2") (pin "2") (pinfunction "2_2") (pintype "passive"))
    )
    (net (code "77") (name "/Row1") (class "Default")
      (node (ref "CPU_CON_2") (pin "13") (pinfunction "13_13") (pintype "passive"))
      (node (ref "Keypad 1") (pin "1") (pinfunction "1_1") (pintype "passive"))
    )
    (net (code "78") (name "/Row2") (class "Default")
      (node (ref "CPU_CON_2") (pin "14") (pinfunction "14_14") (pintype "passive"))
      (node (ref "Keypad 1") (pin "2") (pinfunction "2_2") (pintype "passive"))
    )
    (net (code "79") (name "/Row3") (class "Default")
      (node (ref "CPU_CON_2") (pin "15") (pinfunction "15_15") (pintype "passive"))
      (node (ref "Keypad 1") (pin "3") (pinfunction "3_3") (pintype "passive"))
    )
    (net (code "80") (name "/Row4") (class "Default")
      (node (ref "CPU_CON_2") (pin "16") (pinfunction "16_16") (pintype "passive"))
      (node (ref "Keypad 1") (pin "4") (pinfunction "4_4") (pintype "passive"))
    )
    (net (code "81") (name "/SHT_SCL") (class "Default")
      (node (ref "CPU_CON_2") (pin "11") (pinfunction "11_11") (pintype "passive"))
      (node (ref "SHT1") (pin "2") (pinfunction "2_2") (pintype "passive"))
    )
    (net (code "82") (name "/SHT_SDA") (class "Default")
      (node (ref "CPU_CON_2") (pin "12") (pinfunction "12_12") (pintype "passive"))
      (node (ref "SHT1") (pin "1") (pinfunction "1_1") (pintype "passive"))
    )
    (net (code "83") (name "/Smoke A") (class "Default")
      (node (ref "CPU_CON_3") (pin "9") (pinfunction "9_9") (pintype "passive"))
      (node (ref "Sensor") (pin "5") (pinfunction "5_5") (pintype "passive"))
    )
    (net (code "85") (name "/Smoke Power") (class "Default")
      (node (ref "CPU_CON_3") (pin "20") (pinfunction "20_20") (pintype "passive"))
      (node (ref "Rsmoke") (pin "1") (pinfunction "1_1") (pintype "passive"))
    )
    (net (code "86") (name "/Temp-") (class "Default")
      (node (ref "DC_CON_2") (pin "3") (pinfunction "3_3") (pintype "passive"))
      (node (ref "DC_CON_3") (pin "2") (pinfunction "2_2") (pintype "passive"))
    )
    (net (code "87") (name "/Water A") (class "Default")
      (node (ref "CPU_CON_3") (pin "8") (pinfunction "8_8") (pintype "passive"))
      (node (ref "Sensor") (pin "3") (pinfunction "3_3") (pintype "passive"))
    )
    (net (code "89") (name "GND") (class "Default")
      (node (ref "AC_CON_1") (pin "12") (pinfunction "12_12") (pintype "passive"))
      (node (ref "AC_CON_1") (pin "14") (pinfunction "14_14") (pintype "passive"))
      (node (ref "AC_CON_1") (pin "2") (pinfunction "2_2") (pintype "passive"))
      (node (ref "AC_CON_1") (pin "4") (pinfunction "4_4") (pintype "passive"))
      (node (ref "AIR_CON1") (pin "12") (pinfunction "12_12") (pintype "passive"))
      (node (ref "AIR_CON1") (pin "14") (pinfunction "14_14") (pintype "passive"))
      (node (ref "AIR_CON1") (pin "2") (pinfunction "2_2") (pintype "passive"))
      (node (ref "AIR_CON1") (pin "4") (pinfunction "4_4") (pintype "passive"))
      (node (ref "ATS_CON_1") (pin "12") (pinfunction "12_12") (pintype "passive"))
      (node (ref "ATS_CON_1") (pin "14") (pinfunction "14_14") (pintype "passive"))
      (node (ref "ATS_CON_1") (pin "2") (pinfunction "2_2") (pintype "passive"))
      (node (ref "ATS_CON_1") (pin "4") (pinfunction "4_4") (pintype "passive"))
      (node (ref "CPU_CON_1") (pin "12") (pinfunction "12_12") (pintype "passive"))
      (node (ref "CPU_CON_1") (pin "14") (pinfunction "14_14") (pintype "passive"))
      (node (ref "CPU_CON_1") (pin "2") (pinfunction "2_2") (pintype "passive"))
      (node (ref "CPU_CON_1") (pin "4") (pinfunction "4_4") (pintype "passive"))
      (node (ref "CPU_CON_2") (pin "8") (pinfunction "8_8") (pintype "passive"))
      (node (ref "DC_CON_1") (pin "12") (pinfunction "12_12") (pintype "passive"))
      (node (ref "DC_CON_1") (pin "14") (pinfunction "14_14") (pintype "passive"))
      (node (ref "DC_CON_1") (pin "2") (pinfunction "2_2") (pintype "passive"))
      (node (ref "DC_CON_1") (pin "4") (pinfunction "4_4") (pintype "passive"))
      (node (ref "DC_CON_3") (pin "11") (pinfunction "11_11") (pintype "passive"))
      (node (ref "DC_CON_3") (pin "13") (pinfunction "13_13") (pintype "passive"))
      (node (ref "DC_CON_3") (pin "15") (pinfunction "15_15") (pintype "passive"))
      (node (ref "DC_CON_3") (pin "3") (pinfunction "3_3") (pintype "passive"))
      (node (ref "DC_CON_3") (pin "5") (pinfunction "5_5") (pintype "passive"))
      (node (ref "DC_CON_3") (pin "7") (pinfunction "7_7") (pintype "passive"))
      (node (ref "DC_CON_3") (pin "9") (pinfunction "9_9") (pintype "passive"))
      (node (ref "FAN_CON_1") (pin "12") (pinfunction "12_12") (pintype "passive"))
      (node (ref "FAN_CON_1") (pin "14") (pinfunction "14_14") (pintype "passive"))
      (node (ref "FAN_CON_1") (pin "2") (pinfunction "2_2") (pintype "passive"))
      (node (ref "FAN_CON_1") (pin "4") (pinfunction "4_4") (pintype "passive"))
      (node (ref "GLCD 1") (pin "6") (pinfunction "6_6") (pintype "passive"))
      (node (ref "OMC1") (pin "12") (pinfunction "12_12") (pintype "passive"))
      (node (ref "OMC1") (pin "14") (pinfunction "14_14") (pintype "passive"))
      (node (ref "OMC1") (pin "2") (pinfunction "2_2") (pintype "passive"))
      (node (ref "OMC1") (pin "4") (pinfunction "4_4") (pintype "passive"))
      (node (ref "P2") (pin "1") (pinfunction "1_1") (pintype "passive"))
      (node (ref "P3") (pin "1") (pinfunction "1_1") (pintype "passive"))
      (node (ref "P4") (pin "1") (pinfunction "1_1") (pintype "passive"))
      (node (ref "QBL1") (pin "3") (pinfunction "E_3") (pintype "passive"))
      (node (ref "RGND") (pin "2") (pinfunction "2_2") (pintype "passive"))
      (node (ref "RS485_1") (pin "4") (pinfunction "4_4") (pintype "passive"))
      (node (ref "RS485_2") (pin "4") (pinfunction "4_4") (pintype "passive"))
      (node (ref "RTC1") (pin "6") (pinfunction "6_6") (pintype "passive"))
      (node (ref "SHT1") (pin "4") (pinfunction "4_4") (pintype "passive"))
    )
    (net (code "90") (name "Net-(QBL1-B)") (class "Default")
      (node (ref "QBL1") (pin "1") (pinfunction "B_1") (pintype "passive"))
      (node (ref "RBL1") (pin "2") (pinfunction "2_2") (pintype "passive"))
    )
    (net (code "91") (name "Net-(QBL1-C)") (class "Default")
      (node (ref "GLCD 1") (pin "1") (pinfunction "1_1") (pintype "passive"))
      (node (ref "QBL1") (pin "2") (pinfunction "C_2") (pintype "passive"))
    )
    (net (code "92") (name "Net-(Qsmoke-B)") (class "Default")
      (node (ref "Qsmoke") (pin "1") (pinfunction "B_1") (pintype "passive"))
      (node (ref "Rsmoke") (pin "2") (pinfunction "2_2") (pintype "passive"))
    )
    (net (code "93") (name "Net-(Qsmoke-C)") (class "Default")
      (node (ref "Qsmoke") (pin "2") (pinfunction "C_2") (pintype "passive"))
      (node (ref "Smoke") (pin "2") (pinfunction "2_2") (pintype "passive"))
    )
    (net (code "94") (name "PGND") (class "Default")
      (node (ref "FAN_CON_2") (pin "1") (pinfunction "1_1") (pintype "passive"))
      (node (ref "FAN_CON_2") (pin "11") (pinfunction "11_11") (pintype "passive"))
      (node (ref "FAN_CON_2") (pin "12") (pinfunction "12_12") (pintype "passive"))
      (node (ref "FAN_CON_2") (pin "13") (pinfunction "13_13") (pintype "passive"))
      (node (ref "FAN_CON_2") (pin "14") (pinfunction "14_14") (pintype "passive"))
      (node (ref "FAN_CON_2") (pin "15") (pinfunction "15_15") (pintype "passive"))
      (node (ref "FAN_CON_2") (pin "16") (pinfunction "16_16") (pintype "passive"))
      (node (ref "FAN_CON_2") (pin "17") (pinfunction "17_17") (pintype "passive"))
      (node (ref "FAN_CON_2") (pin "18") (pinfunction "18_18") (pintype "passive"))
      (node (ref "FAN_CON_2") (pin "19") (pinfunction "19_19") (pintype "passive"))
      (node (ref "FAN_CON_2") (pin "2") (pinfunction "2_2") (pintype "passive"))
      (node (ref "FAN_CON_2") (pin "3") (pinfunction "3_3") (pintype "passive"))
      (node (ref "FAN_CON_2") (pin "4") (pinfunction "4_4") (pintype "passive"))
      (node (ref "FAN_CON_2") (pin "5") (pinfunction "5_5") (pintype "passive"))
      (node (ref "FAN_CON_2") (pin "6") (pinfunction "6_6") (pintype "passive"))
      (node (ref "FAN_CON_2") (pin "7") (pinfunction "7_7") (pintype "passive"))
      (node (ref "FAN_CON_2") (pin "8") (pinfunction "8_8") (pintype "passive"))
      (node (ref "FAN_CON_2") (pin "9") (pinfunction "9_9") (pintype "passive"))
      (node (ref "P1") (pin "1") (pinfunction "1_1") (pintype "passive"))
      (node (ref "Qsmoke") (pin "3") (pinfunction "E_3") (pintype "passive"))
      (node (ref "RGND") (pin "1") (pinfunction "1_1") (pintype "passive"))
    )
    (net (code "95") (name "unconnected-(AC_CON_1-Pad8)") (class "Default")
      (node (ref "AC_CON_1") (pin "8") (pinfunction "8_8") (pintype "passive"))
    )
    (net (code "96") (name "unconnected-(AC_CON_1-Pad10)") (class "Default")
      (node (ref "AC_CON_1") (pin "10") (pinfunction "10_10") (pintype "passive"))
    )
    (net (code "97") (name "unconnected-(AC_CON_1-Pad18)") (class "Default")
      (node (ref "AC_CON_1") (pin "18") (pinfunction "18_18") (pintype "passive"))
    )
    (net (code "98") (name "unconnected-(AC_CON_1-Pad20)") (class "Default")
      (node (ref "AC_CON_1") (pin "20") (pinfunction "20_20") (pintype "passive"))
    )
    (net (code "99") (name "unconnected-(AC_CON_2-Pad1)") (class "Default")
      (node (ref "AC_CON_2") (pin "1") (pinfunction "1_1") (pintype "passive"))
    )
    (net (code "100") (name "unconnected-(AC_CON_2-Pad2)") (class "Default")
      (node (ref "AC_CON_2") (pin "2") (pinfunction "2_2") (pintype "passive"))
    )
    (net (code "101") (name "unconnected-(AC_CON_2-Pad3)") (class "Default")
      (node (ref "AC_CON_2") (pin "3") (pinfunction "3_3") (pintype "passive"))
    )
    (net (code "102") (name "unconnected-(AC_CON_2-Pad7)") (class "Default")
      (node (ref "AC_CON_2") (pin "7") (pinfunction "7_7") (pintype "passive"))
    )
    (net (code "103") (name "unconnected-(AC_CON_2-Pad8)") (class "Default")
      (node (ref "AC_CON_2") (pin "8") (pinfunction "8_8") (pintype "passive"))
    )
    (net (code "104") (name "unconnected-(AC_CON_2-Pad11)") (class "Default")
      (node (ref "AC_CON_2") (pin "11") (pinfunction "11_11") (pintype "passive"))
    )
    (net (code "105") (name "unconnected-(AC_CON_2-Pad12)") (class "Default")
      (node (ref "AC_CON_2") (pin "12") (pinfunction "12_12") (pintype "passive"))
    )
    (net (code "106") (name "unconnected-(AC_CON_2-Pad13)") (class "Default")
      (node (ref "AC_CON_2") (pin "13") (pinfunction "13_13") (pintype "passive"))
    )
    (net (code "107") (name "unconnected-(AC_CON_2-Pad14)") (class "Default")
      (node (ref "AC_CON_2") (pin "14") (pinfunction "14_14") (pintype "passive"))
    )
    (net (code "108") (name "unconnected-(AC_CON_2-Pad15)") (class "Default")
      (node (ref "AC_CON_2") (pin "15") (pinfunction "15_15") (pintype "passive"))
    )
    (net (code "109") (name "unconnected-(AC_CON_2-Pad16)") (class "Default")
      (node (ref "AC_CON_2") (pin "16") (pinfunction "16_16") (pintype "passive"))
    )
    (net (code "110") (name "unconnected-(AC_CON_2-Pad17)") (class "Default")
      (node (ref "AC_CON_2") (pin "17") (pinfunction "17_17") (pintype "passive"))
    )
    (net (code "111") (name "unconnected-(AC_CON_2-Pad18)") (class "Default")
      (node (ref "AC_CON_2") (pin "18") (pinfunction "18_18") (pintype "passive"))
    )
    (net (code "112") (name "unconnected-(AC_CON_2-Pad19)") (class "Default")
      (node (ref "AC_CON_2") (pin "19") (pinfunction "19_19") (pintype "passive"))
    )
    (net (code "113") (name "unconnected-(AC_CON_2-Pad20)") (class "Default")
      (node (ref "AC_CON_2") (pin "20") (pinfunction "20_20") (pintype "passive"))
    )
    (net (code "114") (name "unconnected-(AIR_CON1-Pad8)") (class "Default")
      (node (ref "AIR_CON1") (pin "8") (pinfunction "8_8") (pintype "passive"))
    )
    (net (code "115") (name "unconnected-(AIR_CON1-Pad18)") (class "Default")
      (node (ref "AIR_CON1") (pin "18") (pinfunction "18_18") (pintype "passive"))
    )
    (net (code "116") (name "unconnected-(ATS_CON_1-Pad8)") (class "Default")
      (node (ref "ATS_CON_1") (pin "8") (pinfunction "8_8") (pintype "passive"))
    )
    (net (code "117") (name "unconnected-(ATS_CON_1-Pad10)") (class "Default")
      (node (ref "ATS_CON_1") (pin "10") (pinfunction "10_10") (pintype "passive"))
    )
    (net (code "118") (name "unconnected-(ATS_CON_1-Pad18)") (class "Default")
      (node (ref "ATS_CON_1") (pin "18") (pinfunction "18_18") (pintype "passive"))
    )
    (net (code "119") (name "unconnected-(ATS_CON_1-Pad20)") (class "Default")
      (node (ref "ATS_CON_1") (pin "20") (pinfunction "20_20") (pintype "passive"))
    )
    (net (code "120") (name "unconnected-(ATS_CON_2-Pad1)") (class "Default")
      (node (ref "ATS_CON_2") (pin "1") (pinfunction "1_1") (pintype "passive"))
    )
    (net (code "121") (name "unconnected-(ATS_CON_2-Pad2)") (class "Default")
      (node (ref "ATS_CON_2") (pin "2") (pinfunction "2_2") (pintype "passive"))
    )
    (net (code "122") (name "unconnected-(ATS_CON_2-Pad3)") (class "Default")
      (node (ref "ATS_CON_2") (pin "3") (pinfunction "3_3") (pintype "passive"))
    )
    (net (code "123") (name "unconnected-(ATS_CON_2-Pad7)") (class "Default")
      (node (ref "ATS_CON_2") (pin "7") (pinfunction "7_7") (pintype "passive"))
    )
    (net (code "124") (name "unconnected-(ATS_CON_2-Pad8)") (class "Default")
      (node (ref "ATS_CON_2") (pin "8") (pinfunction "8_8") (pintype "passive"))
    )
    (net (code "125") (name "unconnected-(ATS_CON_2-Pad14)") (class "Default")
      (node (ref "ATS_CON_2") (pin "14") (pinfunction "14_14") (pintype "passive"))
    )
    (net (code "126") (name "unconnected-(ATS_CON_2-Pad15)") (class "Default")
      (node (ref "ATS_CON_2") (pin "15") (pinfunction "15_15") (pintype "passive"))
    )
    (net (code "127") (name "unconnected-(ATS_CON_2-Pad16)") (class "Default")
      (node (ref "ATS_CON_2") (pin "16") (pinfunction "16_16") (pintype "passive"))
    )
    (net (code "128") (name "unconnected-(ATS_CON_2-Pad17)") (class "Default")
      (node (ref "ATS_CON_2") (pin "17") (pinfunction "17_17") (pintype "passive"))
    )
    (net (code "129") (name "unconnected-(ATS_CON_2-Pad18)") (class "Default")
      (node (ref "ATS_CON_2") (pin "18") (pinfunction "18_18") (pintype "passive"))
    )
    (net (code "130") (name "unconnected-(ATS_CON_2-Pad19)") (class "Default")
      (node (ref "ATS_CON_2") (pin "19") (pinfunction "19_19") (pintype "passive"))
    )
    (net (code "131") (name "unconnected-(ATS_CON_2-Pad20)") (class "Default")
      (node (ref "ATS_CON_2") (pin "20") (pinfunction "20_20") (pintype "passive"))
    )
    (net (code "132") (name "unconnected-(CPU_AUX_O-Pad1)") (class "Default")
      (node (ref "CPU_AUX_O") (pin "1") (pinfunction "1_1") (pintype "passive"))
    )
    (net (code "133") (name "unconnected-(CPU_CON_1-Pad8)") (class "Default")
      (node (ref "CPU_CON_1") (pin "8") (pinfunction "8_8") (pintype "passive"))
    )
    (net (code "134") (name "unconnected-(CPU_CON_1-Pad10)") (class "Default")
      (node (ref "CPU_CON_1") (pin "10") (pinfunction "10_10") (pintype "passive"))
    )
    (net (code "135") (name "unconnected-(CPU_CON_1-Pad18)") (class "Default")
      (node (ref "CPU_CON_1") (pin "18") (pinfunction "18_18") (pintype "passive"))
    )
    (net (code "136") (name "unconnected-(CPU_CON_1-Pad20)") (class "Default")
      (node (ref "CPU_CON_1") (pin "20") (pinfunction "20_20") (pintype "passive"))
    )
    (net (code "137") (name "unconnected-(CPU_CON_2-Pad9)") (class "Default")
      (node (ref "CPU_CON_2") (pin "9") (pinfunction "9_9") (pintype "passive"))
    )
    (net (code "138") (name "unconnected-(CPU_CON_2-Pad10)") (class "Default")
      (node (ref "CPU_CON_2") (pin "10") (pinfunction "10_10") (pintype "passive"))
    )
    (net (code "139") (name "unconnected-(CPU_CON_3-Pad1)") (class "Default")
      (node (ref "CPU_CON_3") (pin "1") (pinfunction "1_1") (pintype "passive"))
    )
    (net (code "140") (name "unconnected-(CPU_CON_3-Pad2)") (class "Default")
      (node (ref "CPU_CON_3") (pin "2") (pinfunction "2_2") (pintype "passive"))
    )
    (net (code "141") (name "unconnected-(CPU_CON_3-Pad3)") (class "Default")
      (node (ref "CPU_CON_3") (pin "3") (pinfunction "3_3") (pintype "passive"))
    )
    (net (code "142") (name "unconnected-(CPU_CON_3-Pad4)") (class "Default")
      (node (ref "CPU_CON_3") (pin "4") (pinfunction "4_4") (pintype "passive"))
    )
    (net (code "143") (name "unconnected-(CPU_CON_3-Pad5)") (class "Default")
      (node (ref "CPU_CON_3") (pin "5") (pinfunction "5_5") (pintype "passive"))
    )
    (net (code "144") (name "unconnected-(CPU_CON_3-Pad6)") (class "Default")
      (node (ref "CPU_CON_3") (pin "6") (pinfunction "6_6") (pintype "passive"))
    )
    (net (code "145") (name "unconnected-(DC_CON_1-Pad8)") (class "Default")
      (node (ref "DC_CON_1") (pin "8") (pinfunction "8_8") (pintype "passive"))
    )
    (net (code "146") (name "unconnected-(DC_CON_1-Pad10)") (class "Default")
      (node (ref "DC_CON_1") (pin "10") (pinfunction "10_10") (pintype "passive"))
    )
    (net (code "147") (name "unconnected-(DC_CON_1-Pad18)") (class "Default")
      (node (ref "DC_CON_1") (pin "18") (pinfunction "18_18") (pintype "passive"))
    )
    (net (code "148") (name "unconnected-(DC_CON_1-Pad20)") (class "Default")
      (node (ref "DC_CON_1") (pin "20") (pinfunction "20_20") (pintype "passive"))
    )
    (net (code "149") (name "unconnected-(DC_CON_2-Pad1)") (class "Default")
      (node (ref "DC_CON_2") (pin "1") (pinfunction "1_1") (pintype "passive"))
    )
    (net (code "150") (name "unconnected-(DC_CON_2-Pad2)") (class "Default")
      (node (ref "DC_CON_2") (pin "2") (pinfunction "2_2") (pintype "passive"))
    )
    (net (code "151") (name "unconnected-(DC_CON_2-Pad11)") (class "Default")
      (node (ref "DC_CON_2") (pin "11") (pinfunction "11_11") (pintype "passive"))
    )
    (net (code "152") (name "unconnected-(DC_CON_2-Pad12)") (class "Default")
      (node (ref "DC_CON_2") (pin "12") (pinfunction "12_12") (pintype "passive"))
    )
    (net (code "153") (name "unconnected-(DC_CON_2-Pad13)") (class "Default")
      (node (ref "DC_CON_2") (pin "13") (pinfunction "13_13") (pintype "passive"))
    )
    (net (code "154") (name "unconnected-(DC_CON_2-Pad14)") (class "Default")
      (node (ref "DC_CON_2") (pin "14") (pinfunction "14_14") (pintype "passive"))
    )
    (net (code "155") (name "unconnected-(DC_CON_2-Pad15)") (class "Default")
      (node (ref "DC_CON_2") (pin "15") (pinfunction "15_15") (pintype "passive"))
    )
    (net (code "156") (name "unconnected-(DC_CON_2-Pad16)") (class "Default")
      (node (ref "DC_CON_2") (pin "16") (pinfunction "16_16") (pintype "passive"))
    )
    (net (code "157") (name "unconnected-(DC_CON_2-Pad17)") (class "Default")
      (node (ref "DC_CON_2") (pin "17") (pinfunction "17_17") (pintype "passive"))
    )
    (net (code "158") (name "unconnected-(DC_CON_2-Pad18)") (class "Default")
      (node (ref "DC_CON_2") (pin "18") (pinfunction "18_18") (pintype "passive"))
    )
    (net (code "159") (name "unconnected-(DC_CON_2-Pad19)") (class "Default")
      (node (ref "DC_CON_2") (pin "19") (pinfunction "19_19") (pintype "passive"))
    )
    (net (code "160") (name "unconnected-(DC_CON_2-Pad20)") (class "Default")
      (node (ref "DC_CON_2") (pin "20") (pinfunction "20_20") (pintype "passive"))
    )
    (net (code "161") (name "unconnected-(FAN_CON_1-Pad8)") (class "Default")
      (node (ref "FAN_CON_1") (pin "8") (pinfunction "8_8") (pintype "passive"))
    )
    (net (code "162") (name "unconnected-(FAN_CON_1-Pad10)") (class "Default")
      (node (ref "FAN_CON_1") (pin "10") (pinfunction "10_10") (pintype "passive"))
    )
    (net (code "163") (name "unconnected-(FAN_CON_1-Pad18)") (class "Default")
      (node (ref "FAN_CON_1") (pin "18") (pinfunction "18_18") (pintype "passive"))
    )
    (net (code "164") (name "unconnected-(FAN_CON_1-Pad20)") (class "Default")
      (node (ref "FAN_CON_1") (pin "20") (pinfunction "20_20") (pintype "passive"))
    )
    (net (code "165") (name "unconnected-(OMC1-Pad8)") (class "Default")
      (node (ref "OMC1") (pin "8") (pinfunction "8_8") (pintype "passive"))
    )
    (net (code "166") (name "unconnected-(OMC1-Pad10)") (class "Default")
      (node (ref "OMC1") (pin "10") (pinfunction "10_10") (pintype "passive"))
    )
    (net (code "167") (name "unconnected-(OMC1-Pad18)") (class "Default")
      (node (ref "OMC1") (pin "18") (pinfunction "18_18") (pintype "passive"))
    )
    (net (code "168") (name "unconnected-(OMC1-Pad20)") (class "Default")
      (node (ref "OMC1") (pin "20") (pinfunction "20_20") (pintype "passive"))
    )
    (net (code "169") (name "unconnected-(RTC1-Pad1)") (class "Default")
      (node (ref "RTC1") (pin "1") (pinfunction "1_1") (pintype "passive"))
    )
    (net (code "170") (name "unconnected-(RTC1-Pad2)") (class "Default")
      (node (ref "RTC1") (pin "2") (pinfunction "2_2") (pintype "passive"))
    )
  )
)
